# LED.net
KiCad netlist of a schematic drawn in Altium Designer
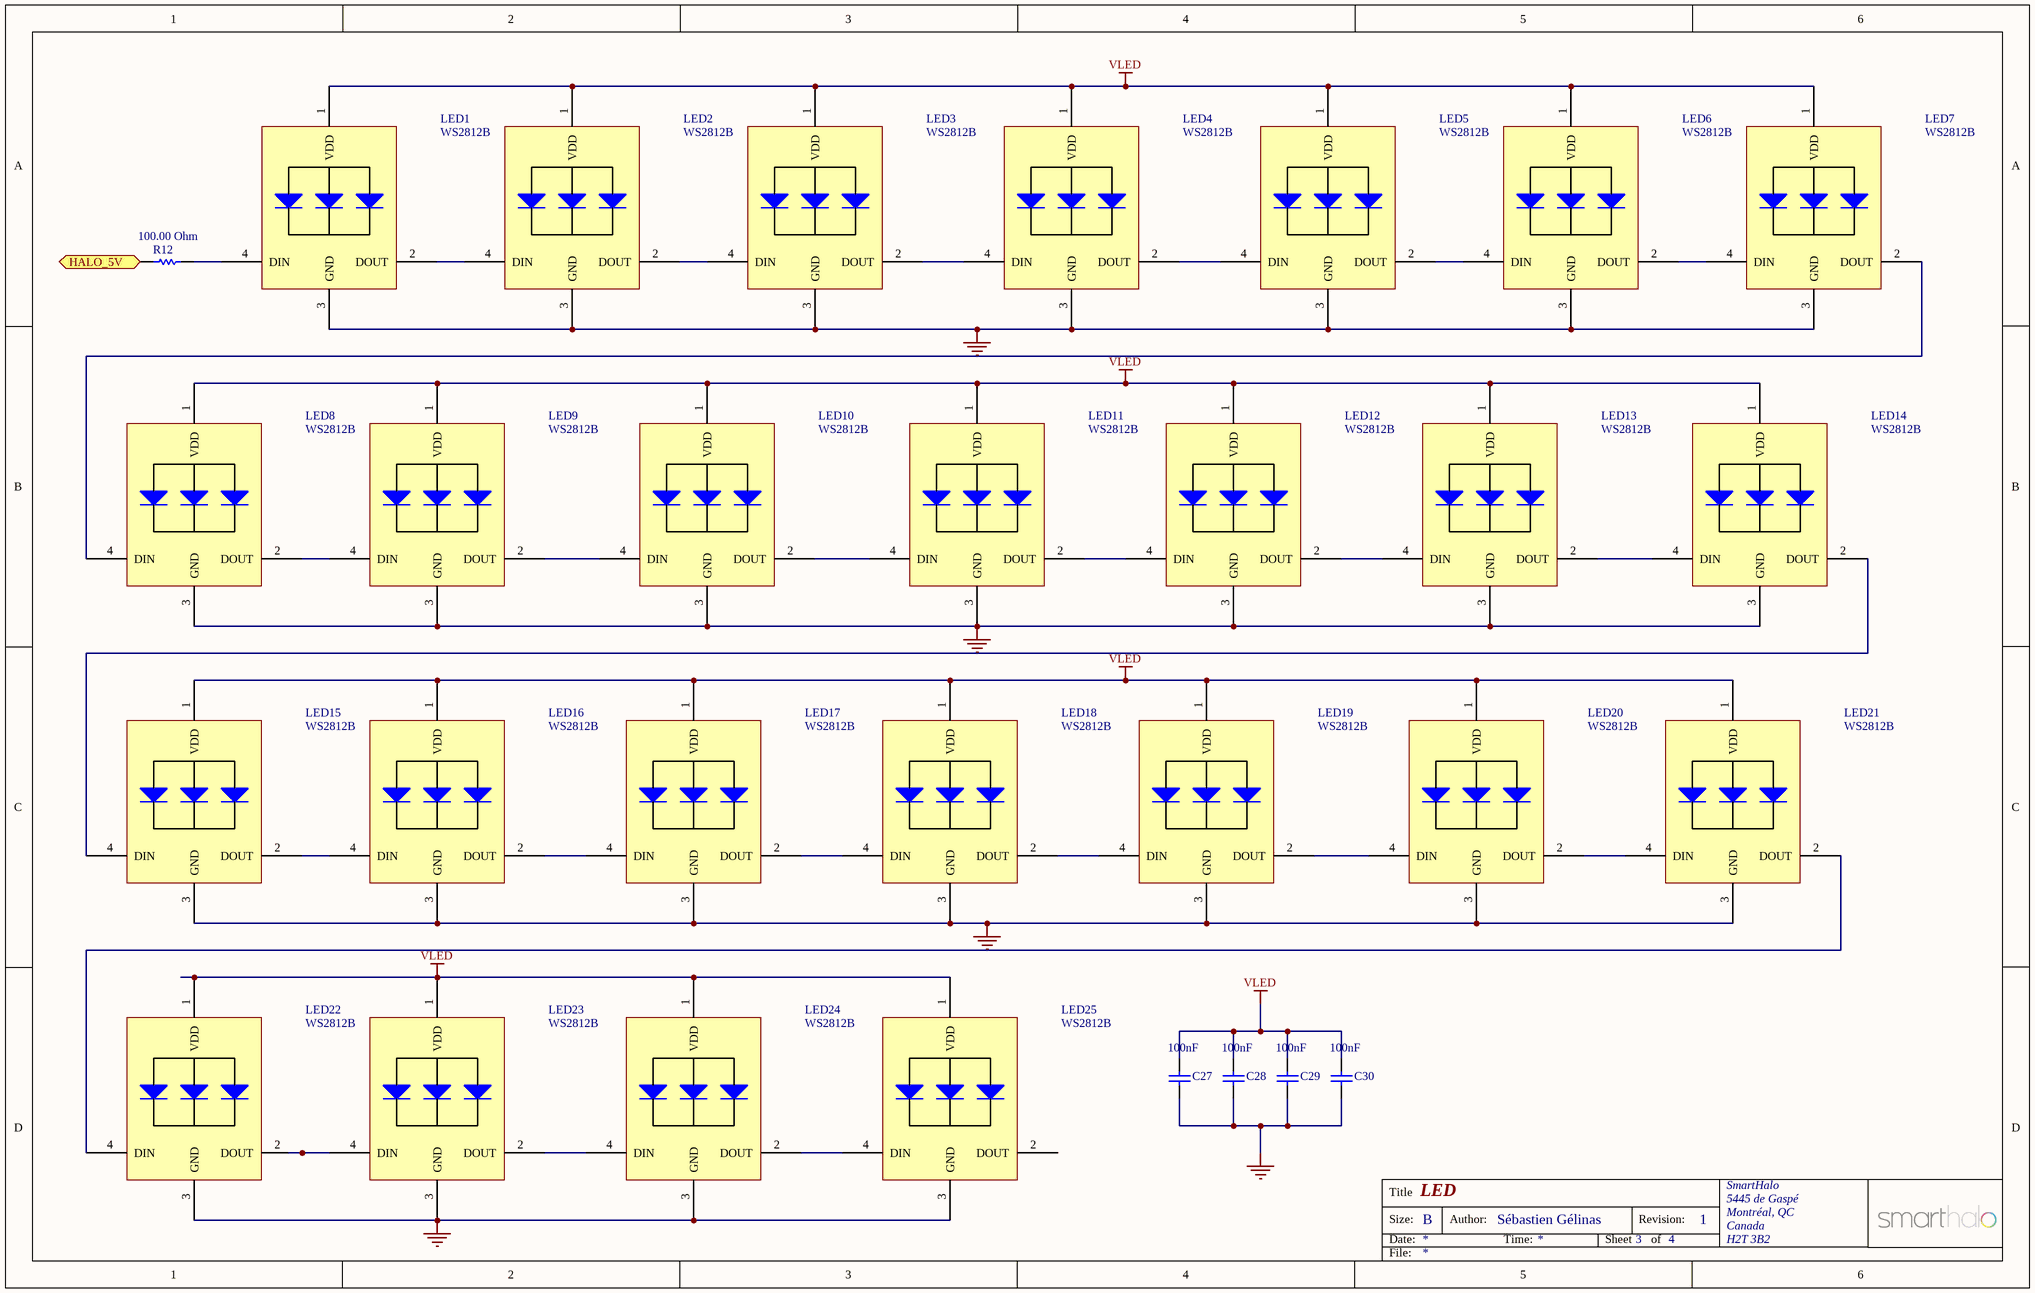
[diagram p0: LED.SchDoc]

(export (version "E")
  (design (tool "Eeschema 10.0.6"))
  (components
    (comp (ref "C27")
      (value "CAP 100nF 10V 0402(1005)")
      (footprint "CAPC0402(1005)60_L")
      (description "CAP 100nF 10V ±5% 0402 (1005 Metric)")
      (fields (field (name "TOLERANCE") "±5%") (field (name "CAPACITANCE") "100nF"))
      (libsource (lib "Altium Content Vault") (part "CMP-1034-02064-1"))
    )
    (comp (ref "C28")
      (value "CAP 100nF 10V 0402(1005)")
      (footprint "CAPC0402(1005)60_L")
      (description "CAP 100nF 10V ±5% 0402 (1005 Metric)")
      (fields (field (name "TOLERANCE") "±5%") (field (name "CAPACITANCE") "100nF"))
      (libsource (lib "Altium Content Vault") (part "CMP-1034-02064-1"))
    )
    (comp (ref "C29")
      (value "CAP 100nF 10V 0402(1005)")
      (footprint "CAPC0402(1005)60_L")
      (description "CAP 100nF 10V ±5% 0402 (1005 Metric)")
      (fields (field (name "TOLERANCE") "±5%") (field (name "CAPACITANCE") "100nF"))
      (libsource (lib "Altium Content Vault") (part "CMP-1034-02064-1"))
    )
    (comp (ref "C30")
      (value "CAP 100nF 10V 0402(1005)")
      (footprint "CAPC0402(1005)60_L")
      (description "CAP 100nF 10V ±5% 0402 (1005 Metric)")
      (fields (field (name "TOLERANCE") "±5%") (field (name "CAPACITANCE") "100nF"))
      (libsource (lib "Altium Content Vault") (part "CMP-1034-02064-1"))
    )
    (comp (ref "LED1")
      (value "WS2812B")
      (footprint "SmartHalo:WS2812B5050")
      (description "IC RGB LED 5V SERIAL")
      (libsource (lib "SmartHalo") (part "WS2812B5050"))
    )
    (comp (ref "LED2")
      (value "WS2812B")
      (footprint "SmartHalo:WS2812B5050")
      (description "IC RGB LED 5V SERIAL")
      (libsource (lib "SmartHalo") (part "WS2812B5050"))
    )
    (comp (ref "LED3")
      (value "WS2812B")
      (footprint "SmartHalo:WS2812B5050")
      (description "IC RGB LED 5V SERIAL")
      (libsource (lib "SmartHalo") (part "WS2812B5050"))
    )
    (comp (ref "LED4")
      (value "WS2812B")
      (footprint "SmartHalo:WS2812B5050")
      (description "IC RGB LED 5V SERIAL")
      (libsource (lib "SmartHalo") (part "WS2812B5050"))
    )
    (comp (ref "LED5")
      (value "WS2812B")
      (footprint "SmartHalo:WS2812B5050")
      (description "IC RGB LED 5V SERIAL")
      (libsource (lib "SmartHalo") (part "WS2812B5050"))
    )
    (comp (ref "LED6")
      (value "WS2812B")
      (footprint "SmartHalo:WS2812B5050")
      (description "IC RGB LED 5V SERIAL")
      (libsource (lib "SmartHalo") (part "WS2812B5050"))
    )
    (comp (ref "LED7")
      (value "WS2812B")
      (footprint "SmartHalo:WS2812B5050")
      (description "IC RGB LED 5V SERIAL")
      (libsource (lib "SmartHalo") (part "WS2812B5050"))
    )
    (comp (ref "LED8")
      (value "WS2812B")
      (footprint "SmartHalo:WS2812B5050")
      (description "IC RGB LED 5V SERIAL")
      (libsource (lib "SmartHalo") (part "WS2812B5050"))
    )
    (comp (ref "LED9")
      (value "WS2812B")
      (footprint "SmartHalo:WS2812B5050")
      (description "IC RGB LED 5V SERIAL")
      (libsource (lib "SmartHalo") (part "WS2812B5050"))
    )
    (comp (ref "LED10")
      (value "WS2812B")
      (footprint "SmartHalo:WS2812B5050")
      (description "IC RGB LED 5V SERIAL")
      (libsource (lib "SmartHalo") (part "WS2812B5050"))
    )
    (comp (ref "LED11")
      (value "WS2812B")
      (footprint "SmartHalo:WS2812B5050")
      (description "IC RGB LED 5V SERIAL")
      (libsource (lib "SmartHalo") (part "WS2812B5050"))
    )
    (comp (ref "LED12")
      (value "WS2812B")
      (footprint "SmartHalo:WS2812B5050")
      (description "IC RGB LED 5V SERIAL")
      (libsource (lib "SmartHalo") (part "WS2812B5050"))
    )
    (comp (ref "LED13")
      (value "WS2812B")
      (footprint "SmartHalo:WS2812B5050")
      (description "IC RGB LED 5V SERIAL")
      (libsource (lib "SmartHalo") (part "WS2812B5050"))
    )
    (comp (ref "LED14")
      (value "WS2812B")
      (footprint "SmartHalo:WS2812B5050")
      (description "IC RGB LED 5V SERIAL")
      (libsource (lib "SmartHalo") (part "WS2812B5050"))
    )
    (comp (ref "LED15")
      (value "WS2812B")
      (footprint "SmartHalo:WS2812B5050")
      (description "IC RGB LED 5V SERIAL")
      (libsource (lib "SmartHalo") (part "WS2812B5050"))
    )
    (comp (ref "LED16")
      (value "WS2812B")
      (footprint "SmartHalo:WS2812B5050")
      (description "IC RGB LED 5V SERIAL")
      (libsource (lib "SmartHalo") (part "WS2812B5050"))
    )
    (comp (ref "LED17")
      (value "WS2812B")
      (footprint "SmartHalo:WS2812B5050")
      (description "IC RGB LED 5V SERIAL")
      (libsource (lib "SmartHalo") (part "WS2812B5050"))
    )
    (comp (ref "LED18")
      (value "WS2812B")
      (footprint "SmartHalo:WS2812B5050")
      (description "IC RGB LED 5V SERIAL")
      (libsource (lib "SmartHalo") (part "WS2812B5050"))
    )
    (comp (ref "LED19")
      (value "WS2812B")
      (footprint "SmartHalo:WS2812B5050")
      (description "IC RGB LED 5V SERIAL")
      (libsource (lib "SmartHalo") (part "WS2812B5050"))
    )
    (comp (ref "LED20")
      (value "WS2812B")
      (footprint "SmartHalo:WS2812B5050")
      (description "IC RGB LED 5V SERIAL")
      (libsource (lib "SmartHalo") (part "WS2812B5050"))
    )
    (comp (ref "LED21")
      (value "WS2812B")
      (footprint "SmartHalo:WS2812B5050")
      (description "IC RGB LED 5V SERIAL")
      (libsource (lib "SmartHalo") (part "WS2812B5050"))
    )
    (comp (ref "LED22")
      (value "WS2812B")
      (footprint "SmartHalo:WS2812B5050")
      (description "IC RGB LED 5V SERIAL")
      (libsource (lib "SmartHalo") (part "WS2812B5050"))
    )
    (comp (ref "LED23")
      (value "WS2812B")
      (footprint "SmartHalo:WS2812B5050")
      (description "IC RGB LED 5V SERIAL")
      (libsource (lib "SmartHalo") (part "WS2812B5050"))
    )
    (comp (ref "LED24")
      (value "WS2812B")
      (footprint "SmartHalo:WS2812B5050")
      (description "IC RGB LED 5V SERIAL")
      (libsource (lib "SmartHalo") (part "WS2812B5050"))
    )
    (comp (ref "LED25")
      (value "WS2812B")
      (footprint "SmartHalo:WS2812B5050")
      (description "IC RGB LED 5V SERIAL")
      (libsource (lib "SmartHalo") (part "WS2812B5050"))
    )
    (comp (ref "R12")
      (value "100R ±5% 0402(1005)")
      (footprint "RESC0402(1005)_L")
      (description "100R 0.063W ±5% 0402 (1005 Metric)")
      (fields
        (field (name "POWER") "0.063 W")
        (field (name "RESISTANCE") "100.00 Ohm")
        (field (name "TOLERANCE") "±5 %")
      )
      (libsource (lib "Altium Content Vault") (part "CMP-1011-00050-1"))
    )
  )
  (nets
    (net (code "1") (name "/HALO_5V") (class "Default")
      (node (ref "R12") (pin "1") (pinfunction "1_1") (pintype "passive"))
    )
    (net (code "2") (name "GND") (class "Default")
      (node (ref "C27") (pin "1") (pinfunction "1_1") (pintype "passive"))
      (node (ref "C28") (pin "1") (pinfunction "1_1") (pintype "passive"))
      (node (ref "C29") (pin "1") (pinfunction "1_1") (pintype "passive"))
      (node (ref "C30") (pin "1") (pinfunction "1_1") (pintype "passive"))
      (node (ref "LED1") (pin "3") (pinfunction "GND_3") (pintype "passive"))
      (node (ref "LED10") (pin "3") (pinfunction "GND_3") (pintype "passive"))
      (node (ref "LED11") (pin "3") (pinfunction "GND_3") (pintype "passive"))
      (node (ref "LED12") (pin "3") (pinfunction "GND_3") (pintype "passive"))
      (node (ref "LED13") (pin "3") (pinfunction "GND_3") (pintype "passive"))
      (node (ref "LED14") (pin "3") (pinfunction "GND_3") (pintype "passive"))
      (node (ref "LED15") (pin "3") (pinfunction "GND_3") (pintype "passive"))
      (node (ref "LED16") (pin "3") (pinfunction "GND_3") (pintype "passive"))
      (node (ref "LED17") (pin "3") (pinfunction "GND_3") (pintype "passive"))
      (node (ref "LED18") (pin "3") (pinfunction "GND_3") (pintype "passive"))
      (node (ref "LED19") (pin "3") (pinfunction "GND_3") (pintype "passive"))
      (node (ref "LED2") (pin "3") (pinfunction "GND_3") (pintype "passive"))
      (node (ref "LED20") (pin "3") (pinfunction "GND_3") (pintype "passive"))
      (node (ref "LED21") (pin "3") (pinfunction "GND_3") (pintype "passive"))
      (node (ref "LED22") (pin "3") (pinfunction "GND_3") (pintype "passive"))
      (node (ref "LED23") (pin "3") (pinfunction "GND_3") (pintype "passive"))
      (node (ref "LED24") (pin "3") (pinfunction "GND_3") (pintype "passive"))
      (node (ref "LED25") (pin "3") (pinfunction "GND_3") (pintype "passive"))
      (node (ref "LED3") (pin "3") (pinfunction "GND_3") (pintype "passive"))
      (node (ref "LED4") (pin "3") (pinfunction "GND_3") (pintype "passive"))
      (node (ref "LED5") (pin "3") (pinfunction "GND_3") (pintype "passive"))
      (node (ref "LED6") (pin "3") (pinfunction "GND_3") (pintype "passive"))
      (node (ref "LED7") (pin "3") (pinfunction "GND_3") (pintype "passive"))
      (node (ref "LED8") (pin "3") (pinfunction "GND_3") (pintype "passive"))
      (node (ref "LED9") (pin "3") (pinfunction "GND_3") (pintype "passive"))
    )
    (net (code "3") (name "Net-(LED1-DIN)") (class "Default")
      (node (ref "LED1") (pin "4") (pinfunction "DIN_4") (pintype "passive"))
      (node (ref "R12") (pin "2") (pinfunction "2_2") (pintype "passive"))
    )
    (net (code "4") (name "Net-(LED1-DOUT)") (class "Default")
      (node (ref "LED1") (pin "2") (pinfunction "DOUT_2") (pintype "passive"))
      (node (ref "LED2") (pin "4") (pinfunction "DIN_4") (pintype "passive"))
    )
    (net (code "5") (name "Net-(LED2-DOUT)") (class "Default")
      (node (ref "LED2") (pin "2") (pinfunction "DOUT_2") (pintype "passive"))
      (node (ref "LED3") (pin "4") (pinfunction "DIN_4") (pintype "passive"))
    )
    (net (code "6") (name "Net-(LED3-DOUT)") (class "Default")
      (node (ref "LED3") (pin "2") (pinfunction "DOUT_2") (pintype "passive"))
      (node (ref "LED4") (pin "4") (pinfunction "DIN_4") (pintype "passive"))
    )
    (net (code "7") (name "Net-(LED4-DOUT)") (class "Default")
      (node (ref "LED4") (pin "2") (pinfunction "DOUT_2") (pintype "passive"))
      (node (ref "LED5") (pin "4") (pinfunction "DIN_4") (pintype "passive"))
    )
    (net (code "8") (name "Net-(LED5-DOUT)") (class "Default")
      (node (ref "LED5") (pin "2") (pinfunction "DOUT_2") (pintype "passive"))
      (node (ref "LED6") (pin "4") (pinfunction "DIN_4") (pintype "passive"))
    )
    (net (code "9") (name "Net-(LED6-DOUT)") (class "Default")
      (node (ref "LED6") (pin "2") (pinfunction "DOUT_2") (pintype "passive"))
      (node (ref "LED7") (pin "4") (pinfunction "DIN_4") (pintype "passive"))
    )
    (net (code "10") (name "Net-(LED7-DOUT)") (class "Default")
      (node (ref "LED7") (pin "2") (pinfunction "DOUT_2") (pintype "passive"))
      (node (ref "LED8") (pin "4") (pinfunction "DIN_4") (pintype "passive"))
    )
    (net (code "11") (name "Net-(LED8-DOUT)") (class "Default")
      (node (ref "LED8") (pin "2") (pinfunction "DOUT_2") (pintype "passive"))
      (node (ref "LED9") (pin "4") (pinfunction "DIN_4") (pintype "passive"))
    )
    (net (code "12") (name "Net-(LED10-DIN)") (class "Default")
      (node (ref "LED10") (pin "4") (pinfunction "DIN_4") (pintype "passive"))
      (node (ref "LED9") (pin "2") (pinfunction "DOUT_2") (pintype "passive"))
    )
    (net (code "13") (name "Net-(LED10-DOUT)") (class "Default")
      (node (ref "LED10") (pin "2") (pinfunction "DOUT_2") (pintype "passive"))
      (node (ref "LED11") (pin "4") (pinfunction "DIN_4") (pintype "passive"))
    )
    (net (code "14") (name "Net-(LED11-DOUT)") (class "Default")
      (node (ref "LED11") (pin "2") (pinfunction "DOUT_2") (pintype "passive"))
      (node (ref "LED12") (pin "4") (pinfunction "DIN_4") (pintype "passive"))
    )
    (net (code "15") (name "Net-(LED12-DOUT)") (class "Default")
      (node (ref "LED12") (pin "2") (pinfunction "DOUT_2") (pintype "passive"))
      (node (ref "LED13") (pin "4") (pinfunction "DIN_4") (pintype "passive"))
    )
    (net (code "16") (name "Net-(LED13-DOUT)") (class "Default")
      (node (ref "LED13") (pin "2") (pinfunction "DOUT_2") (pintype "passive"))
      (node (ref "LED14") (pin "4") (pinfunction "DIN_4") (pintype "passive"))
    )
    (net (code "17") (name "Net-(LED14-DOUT)") (class "Default")
      (node (ref "LED14") (pin "2") (pinfunction "DOUT_2") (pintype "passive"))
      (node (ref "LED15") (pin "4") (pinfunction "DIN_4") (pintype "passive"))
    )
    (net (code "18") (name "Net-(LED15-DOUT)") (class "Default")
      (node (ref "LED15") (pin "2") (pinfunction "DOUT_2") (pintype "passive"))
      (node (ref "LED16") (pin "4") (pinfunction "DIN_4") (pintype "passive"))
    )
    (net (code "19") (name "Net-(LED16-DOUT)") (class "Default")
      (node (ref "LED16") (pin "2") (pinfunction "DOUT_2") (pintype "passive"))
      (node (ref "LED17") (pin "4") (pinfunction "DIN_4") (pintype "passive"))
    )
    (net (code "20") (name "Net-(LED17-DOUT)") (class "Default")
      (node (ref "LED17") (pin "2") (pinfunction "DOUT_2") (pintype "passive"))
      (node (ref "LED18") (pin "4") (pinfunction "DIN_4") (pintype "passive"))
    )
    (net (code "21") (name "Net-(LED18-DOUT)") (class "Default")
      (node (ref "LED18") (pin "2") (pinfunction "DOUT_2") (pintype "passive"))
      (node (ref "LED19") (pin "4") (pinfunction "DIN_4") (pintype "passive"))
    )
    (net (code "22") (name "Net-(LED19-DOUT)") (class "Default")
      (node (ref "LED19") (pin "2") (pinfunction "DOUT_2") (pintype "passive"))
      (node (ref "LED20") (pin "4") (pinfunction "DIN_4") (pintype "passive"))
    )
    (net (code "23") (name "Net-(LED20-DOUT)") (class "Default")
      (node (ref "LED20") (pin "2") (pinfunction "DOUT_2") (pintype "passive"))
      (node (ref "LED21") (pin "4") (pinfunction "DIN_4") (pintype "passive"))
    )
    (net (code "24") (name "Net-(LED21-DOUT)") (class "Default")
      (node (ref "LED21") (pin "2") (pinfunction "DOUT_2") (pintype "passive"))
      (node (ref "LED22") (pin "4") (pinfunction "DIN_4") (pintype "passive"))
    )
    (net (code "25") (name "Net-(LED22-DOUT)") (class "Default")
      (node (ref "LED22") (pin "2") (pinfunction "DOUT_2") (pintype "passive"))
      (node (ref "LED23") (pin "4") (pinfunction "DIN_4") (pintype "passive"))
    )
    (net (code "26") (name "Net-(LED23-DOUT)") (class "Default")
      (node (ref "LED23") (pin "2") (pinfunction "DOUT_2") (pintype "passive"))
      (node (ref "LED24") (pin "4") (pinfunction "DIN_4") (pintype "passive"))
    )
    (net (code "27") (name "Net-(LED24-DOUT)") (class "Default")
      (node (ref "LED24") (pin "2") (pinfunction "DOUT_2") (pintype "passive"))
      (node (ref "LED25") (pin "4") (pinfunction "DIN_4") (pintype "passive"))
    )
    (net (code "28") (name "VLED") (class "Default")
      (node (ref "C27") (pin "2") (pinfunction "2_2") (pintype "passive"))
      (node (ref "C28") (pin "2") (pinfunction "2_2") (pintype "passive"))
      (node (ref "C29") (pin "2") (pinfunction "2_2") (pintype "passive"))
      (node (ref "C30") (pin "2") (pinfunction "2_2") (pintype "passive"))
      (node (ref "LED1") (pin "1") (pinfunction "VDD_1") (pintype "passive"))
      (node (ref "LED10") (pin "1") (pinfunction "VDD_1") (pintype "passive"))
      (node (ref "LED11") (pin "1") (pinfunction "VDD_1") (pintype "passive"))
      (node (ref "LED12") (pin "1") (pinfunction "VDD_1") (pintype "passive"))
      (node (ref "LED13") (pin "1") (pinfunction "VDD_1") (pintype "passive"))
      (node (ref "LED14") (pin "1") (pinfunction "VDD_1") (pintype "passive"))
      (node (ref "LED15") (pin "1") (pinfunction "VDD_1") (pintype "passive"))
      (node (ref "LED16") (pin "1") (pinfunction "VDD_1") (pintype "passive"))
      (node (ref "LED17") (pin "1") (pinfunction "VDD_1") (pintype "passive"))
      (node (ref "LED18") (pin "1") (pinfunction "VDD_1") (pintype "passive"))
      (node (ref "LED19") (pin "1") (pinfunction "VDD_1") (pintype "passive"))
      (node (ref "LED2") (pin "1") (pinfunction "VDD_1") (pintype "passive"))
      (node (ref "LED20") (pin "1") (pinfunction "VDD_1") (pintype "passive"))
      (node (ref "LED21") (pin "1") (pinfunction "VDD_1") (pintype "passive"))
      (node (ref "LED22") (pin "1") (pinfunction "VDD_1") (pintype "passive"))
      (node (ref "LED23") (pin "1") (pinfunction "VDD_1") (pintype "passive"))
      (node (ref "LED24") (pin "1") (pinfunction "VDD_1") (pintype "passive"))
      (node (ref "LED25") (pin "1") (pinfunction "VDD_1") (pintype "passive"))
      (node (ref "LED3") (pin "1") (pinfunction "VDD_1") (pintype "passive"))
      (node (ref "LED4") (pin "1") (pinfunction "VDD_1") (pintype "passive"))
      (node (ref "LED5") (pin "1") (pinfunction "VDD_1") (pintype "passive"))
      (node (ref "LED6") (pin "1") (pinfunction "VDD_1") (pintype "passive"))
      (node (ref "LED7") (pin "1") (pinfunction "VDD_1") (pintype "passive"))
      (node (ref "LED8") (pin "1") (pinfunction "VDD_1") (pintype "passive"))
      (node (ref "LED9") (pin "1") (pinfunction "VDD_1") (pintype "passive"))
    )
    (net (code "29") (name "unconnected-(LED25-DOUT-Pad2)") (class "Default")
      (node (ref "LED25") (pin "2") (pinfunction "DOUT_2") (pintype "passive"))
    )
  )
)
